# LCD_KB_SOUND.net
KiCad netlist of a schematic drawn in Altium Designer
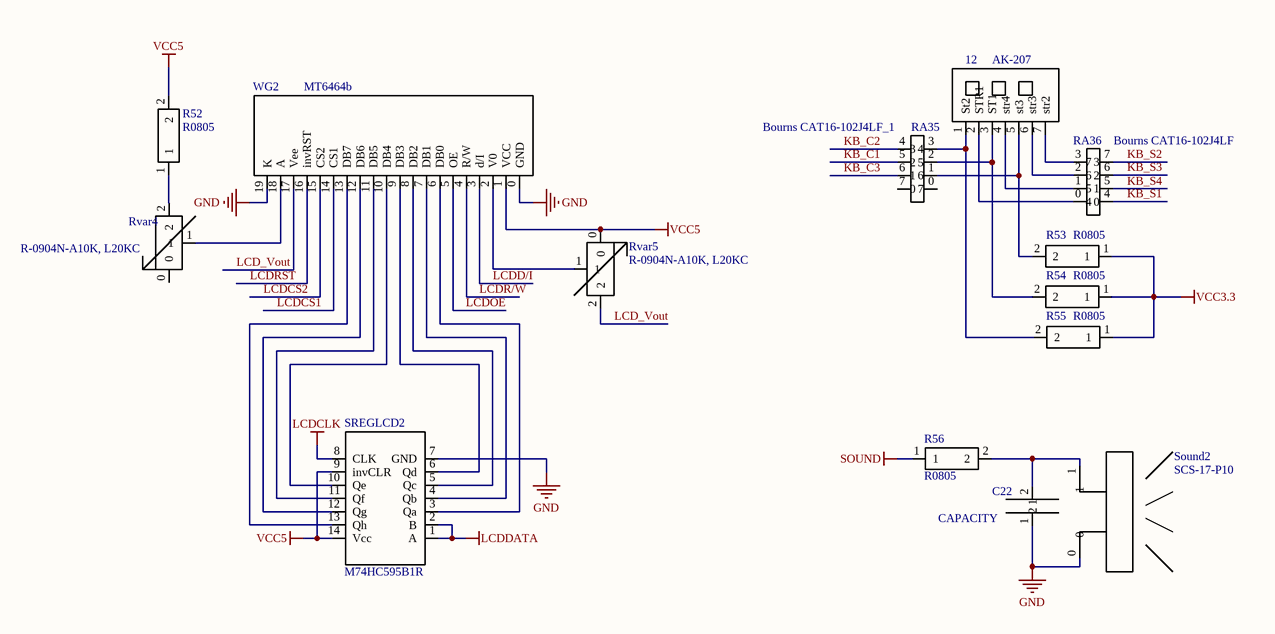
[diagram p0: LCD_KB_SOUND.SchDoc]

(export (version "E")
  (design (tool "Eeschema 10.0.6"))
  (components
    (comp (ref "12")
      (value "AK-207")
      (footprint "PcbLib1:AK-207")
      (libsource (lib "Library") (part "AK-207"))
    )
    (comp (ref "C22")
      (value "CAPACITY")
      (footprint "PcbLib1:R0805")
      (libsource (lib "Library") (part "CAPACITY"))
    )
    (comp (ref "R52") (value "R0805") (footprint "PcbLib1:R0805") (libsource (lib "Library") (part "R0805")))
    (comp (ref "R53") (value "R0805") (footprint "PcbLib1:R0805") (libsource (lib "Library") (part "R0805")))
    (comp (ref "R54") (value "R0805") (footprint "PcbLib1:R0805") (libsource (lib "Library") (part "R0805")))
    (comp (ref "R55") (value "R0805") (footprint "PcbLib1:R0805") (libsource (lib "Library") (part "R0805")))
    (comp (ref "R56") (value "R0805") (footprint "PcbLib1:R0805") (libsource (lib "Library") (part "R0805")))
    (comp (ref "RA35")
      (value "Bourns CAT16-102J4LF_1")
      (footprint "PcbLib1:CAT16-102J4LF_2")
      (libsource (lib "Library") (part "Bourns CAT16-102J4LF_1"))
    )
    (comp (ref "RA36")
      (value "Bourns CAT16-102J4LF")
      (footprint "PcbLib1:CAT16-102J4LF")
      (libsource (lib "Library") (part "Bourns CAT16-102J4LF"))
    )
    (comp (ref "Rvar4")
      (value "R-0904N-A10K, L20KC")
      (footprint "PcbLib1:R-0904N-A10K, L20KC")
      (libsource (lib "Library") (part "R-0904N-A10K, L20KC"))
    )
    (comp (ref "Rvar5")
      (value "R-0904N-A10K, L20KC")
      (footprint "PcbLib1:R-0904N-A10K, L20KC")
      (libsource (lib "Library") (part "R-0904N-A10K, L20KC"))
    )
    (comp (ref "Sound2")
      (value "SCS-17-P10")
      (footprint "PcbLib1:SCS-17-P10")
      (libsource (lib "Library") (part "SCS-17-P10"))
    )
    (comp (ref "SREGLCD2")
      (value "M74HC595B1R")
      (footprint "PcbLib1:SN74HC164DRX")
      (libsource (lib "Library") (part "M74HC595B1R"))
    )
    (comp (ref "WG2")
      (value "MT6464b")
      (footprint "PcbLib1:WG12864A")
      (libsource (lib "Library") (part "MT6464b"))
    )
  )
  (nets
    (net (code "1") (name "/KB_C1") (class "Default")
      (node (ref "RA35") (pin "5") (pinfunction "5_5") (pintype "passive"))
    )
    (net (code "2") (name "/KB_C2") (class "Default")
      (node (ref "RA35") (pin "4") (pinfunction "4_4") (pintype "passive"))
    )
    (net (code "3") (name "/KB_C3") (class "Default")
      (node (ref "RA35") (pin "6") (pinfunction "6_6") (pintype "passive"))
    )
    (net (code "4") (name "/KB_S1") (class "Default")
      (node (ref "RA36") (pin "4") (pinfunction "4_4") (pintype "passive"))
    )
    (net (code "5") (name "/KB_S2") (class "Default")
      (node (ref "RA36") (pin "7") (pinfunction "7_7") (pintype "passive"))
    )
    (net (code "6") (name "/KB_S3") (class "Default")
      (node (ref "RA36") (pin "6") (pinfunction "6_6") (pintype "passive"))
    )
    (net (code "8") (name "/KB_S4") (class "Default")
      (node (ref "RA36") (pin "5") (pinfunction "5_5") (pintype "passive"))
    )
    (net (code "9") (name "/LCDCS1") (class "Default")
      (node (ref "WG2") (pin "14") (pinfunction "CS1_14") (pintype "passive"))
    )
    (net (code "10") (name "/LCDCS2") (class "Default")
      (node (ref "WG2") (pin "15") (pinfunction "CS2_15") (pintype "passive"))
    )
    (net (code "11") (name "/LCDD{slash}I") (class "Default")
      (node (ref "WG2") (pin "3") (pinfunction "d/I_3") (pintype "passive"))
    )
    (net (code "12") (name "/LCDOE") (class "Default")
      (node (ref "WG2") (pin "5") (pinfunction "OE_5") (pintype "passive"))
    )
    (net (code "13") (name "/LCDRST") (class "Default")
      (node (ref "WG2") (pin "16") (pinfunction "invRST_16") (pintype "passive"))
    )
    (net (code "14") (name "/LCDR{slash}W") (class "Default")
      (node (ref "WG2") (pin "4") (pinfunction "R/W_4") (pintype "passive"))
    )
    (net (code "15") (name "/LCD_Vout") (class "Default")
      (node (ref "Rvar5") (pin "2") (pinfunction "2_2") (pintype "passive"))
      (node (ref "WG2") (pin "17") (pinfunction "Vee_17") (pintype "passive"))
    )
    (net (code "16") (name "GND") (class "Default")
      (node (ref "C22") (pin "1") (pinfunction "1_1") (pintype "passive"))
      (node (ref "SREGLCD2") (pin "7") (pinfunction "GND_7") (pintype "passive"))
      (node (ref "Sound2") (pin "0") (pinfunction "0_0") (pintype "passive"))
      (node (ref "WG2") (pin "0") (pinfunction "GND_0") (pintype "passive"))
      (node (ref "WG2") (pin "19") (pinfunction "K_19") (pintype "passive"))
    )
    (net (code "17") (name "LCDCLK") (class "Default")
      (node (ref "SREGLCD2") (pin "8") (pinfunction "CLK_8") (pintype "passive"))
    )
    (net (code "18") (name "LCDDATA") (class "Default")
      (node (ref "SREGLCD2") (pin "1") (pinfunction "A_1") (pintype "passive"))
      (node (ref "SREGLCD2") (pin "2") (pinfunction "B_2") (pintype "passive"))
    )
    (net (code "19") (name "Net-(12-ST1)") (class "Default")
      (node (ref "12") (pin "3") (pinfunction "ST1_3") (pintype "passive"))
      (node (ref "R54") (pin "2") (pinfunction "2_2") (pintype "passive"))
      (node (ref "RA35") (pin "2") (pinfunction "2_2") (pintype "passive"))
    )
    (net (code "20") (name "Net-(12-STR1)") (class "Default")
      (node (ref "12") (pin "2") (pinfunction "STR1_2") (pintype "passive"))
      (node (ref "RA36") (pin "0") (pinfunction "0_0") (pintype "passive"))
    )
    (net (code "21") (name "Net-(12-St2)") (class "Default")
      (node (ref "12") (pin "1") (pinfunction "St2_1") (pintype "passive"))
      (node (ref "R55") (pin "2") (pinfunction "2_2") (pintype "passive"))
      (node (ref "RA35") (pin "3") (pinfunction "3_3") (pintype "passive"))
    )
    (net (code "22") (name "Net-(12-st3)") (class "Default")
      (node (ref "12") (pin "5") (pinfunction "st3_5") (pintype "passive"))
      (node (ref "R53") (pin "2") (pinfunction "2_2") (pintype "passive"))
      (node (ref "RA35") (pin "1") (pinfunction "1_1") (pintype "passive"))
    )
    (net (code "23") (name "Net-(12-str2)") (class "Default")
      (node (ref "12") (pin "7") (pinfunction "str2_7") (pintype "passive"))
      (node (ref "RA36") (pin "3") (pinfunction "3_3") (pintype "passive"))
    )
    (net (code "24") (name "Net-(12-str3)") (class "Default")
      (node (ref "12") (pin "6") (pinfunction "str3_6") (pintype "passive"))
      (node (ref "RA36") (pin "2") (pinfunction "2_2") (pintype "passive"))
    )
    (net (code "25") (name "Net-(12-str4)") (class "Default")
      (node (ref "12") (pin "4") (pinfunction "str4_4") (pintype "passive"))
      (node (ref "RA36") (pin "1") (pinfunction "1_1") (pintype "passive"))
    )
    (net (code "26") (name "Net-(C22-Pad2)") (class "Default")
      (node (ref "C22") (pin "2") (pinfunction "2_2") (pintype "passive"))
      (node (ref "R56") (pin "2") (pinfunction "2_2") (pintype "passive"))
      (node (ref "Sound2") (pin "1") (pinfunction "1_1") (pintype "passive"))
    )
    (net (code "27") (name "Net-(R52-Pad1)") (class "Default")
      (node (ref "R52") (pin "1") (pinfunction "1_1") (pintype "passive"))
      (node (ref "Rvar4") (pin "2") (pinfunction "2_2") (pintype "passive"))
    )
    (net (code "28") (name "Net-(SREGLCD2-Qa)") (class "Default")
      (node (ref "SREGLCD2") (pin "3") (pinfunction "Qa_3") (pintype "passive"))
      (node (ref "WG2") (pin "6") (pinfunction "DB0_6") (pintype "passive"))
    )
    (net (code "29") (name "Net-(SREGLCD2-Qb)") (class "Default")
      (node (ref "SREGLCD2") (pin "4") (pinfunction "Qb_4") (pintype "passive"))
      (node (ref "WG2") (pin "7") (pinfunction "DB1_7") (pintype "passive"))
    )
    (net (code "30") (name "Net-(SREGLCD2-Qc)") (class "Default")
      (node (ref "SREGLCD2") (pin "5") (pinfunction "Qc_5") (pintype "passive"))
      (node (ref "WG2") (pin "8") (pinfunction "DB2_8") (pintype "passive"))
    )
    (net (code "31") (name "Net-(SREGLCD2-Qd)") (class "Default")
      (node (ref "SREGLCD2") (pin "6") (pinfunction "Qd_6") (pintype "passive"))
      (node (ref "WG2") (pin "9") (pinfunction "DB3_9") (pintype "passive"))
    )
    (net (code "32") (name "Net-(SREGLCD2-Qe)") (class "Default")
      (node (ref "SREGLCD2") (pin "10") (pinfunction "Qe_10") (pintype "passive"))
      (node (ref "WG2") (pin "10") (pinfunction "DB4_10") (pintype "passive"))
    )
    (net (code "33") (name "Net-(SREGLCD2-Qf)") (class "Default")
      (node (ref "SREGLCD2") (pin "11") (pinfunction "Qf_11") (pintype "passive"))
      (node (ref "WG2") (pin "11") (pinfunction "DB5_11") (pintype "passive"))
    )
    (net (code "34") (name "Net-(SREGLCD2-Qg)") (class "Default")
      (node (ref "SREGLCD2") (pin "12") (pinfunction "Qg_12") (pintype "passive"))
      (node (ref "WG2") (pin "12") (pinfunction "DB6_12") (pintype "passive"))
    )
    (net (code "35") (name "Net-(SREGLCD2-Qh)") (class "Default")
      (node (ref "SREGLCD2") (pin "13") (pinfunction "Qh_13") (pintype "passive"))
      (node (ref "WG2") (pin "13") (pinfunction "DB7_13") (pintype "passive"))
    )
    (net (code "36") (name "Net-(WG2-A)") (class "Default")
      (node (ref "Rvar4") (pin "1") (pinfunction "1_1") (pintype "passive"))
      (node (ref "WG2") (pin "18") (pinfunction "A_18") (pintype "passive"))
    )
    (net (code "37") (name "Net-(WG2-V0)") (class "Default")
      (node (ref "Rvar5") (pin "1") (pinfunction "1_1") (pintype "passive"))
      (node (ref "WG2") (pin "2") (pinfunction "V0_2") (pintype "passive"))
    )
    (net (code "38") (name "SOUND") (class "Default")
      (node (ref "R56") (pin "1") (pinfunction "1_1") (pintype "passive"))
    )
    (net (code "39") (name "VCC3.3") (class "Default")
      (node (ref "R53") (pin "1") (pinfunction "1_1") (pintype "passive"))
      (node (ref "R54") (pin "1") (pinfunction "1_1") (pintype "passive"))
      (node (ref "R55") (pin "1") (pinfunction "1_1") (pintype "passive"))
    )
    (net (code "40") (name "VCC5") (class "Default")
      (node (ref "R52") (pin "2") (pinfunction "2_2") (pintype "passive"))
      (node (ref "Rvar5") (pin "0") (pinfunction "0_0") (pintype "passive"))
      (node (ref "SREGLCD2") (pin "14") (pinfunction "Vcc_14") (pintype "passive"))
      (node (ref "SREGLCD2") (pin "9") (pinfunction "invCLR_9") (pintype "passive"))
      (node (ref "WG2") (pin "1") (pinfunction "VCC_1") (pintype "passive"))
    )
    (net (code "41") (name "unconnected-(RA35-Pad0)") (class "Default")
      (node (ref "RA35") (pin "0") (pinfunction "0_0") (pintype "passive"))
    )
    (net (code "42") (name "unconnected-(RA35-Pad7)") (class "Default")
      (node (ref "RA35") (pin "7") (pinfunction "7_7") (pintype "passive"))
    )
    (net (code "43") (name "unconnected-(Rvar4-Pad0)") (class "Default")
      (node (ref "Rvar4") (pin "0") (pinfunction "0_0") (pintype "passive"))
    )
  )
)
